# Adapter-IOX-test.net
KiCad netlist of a schematic drawn in EAGLE
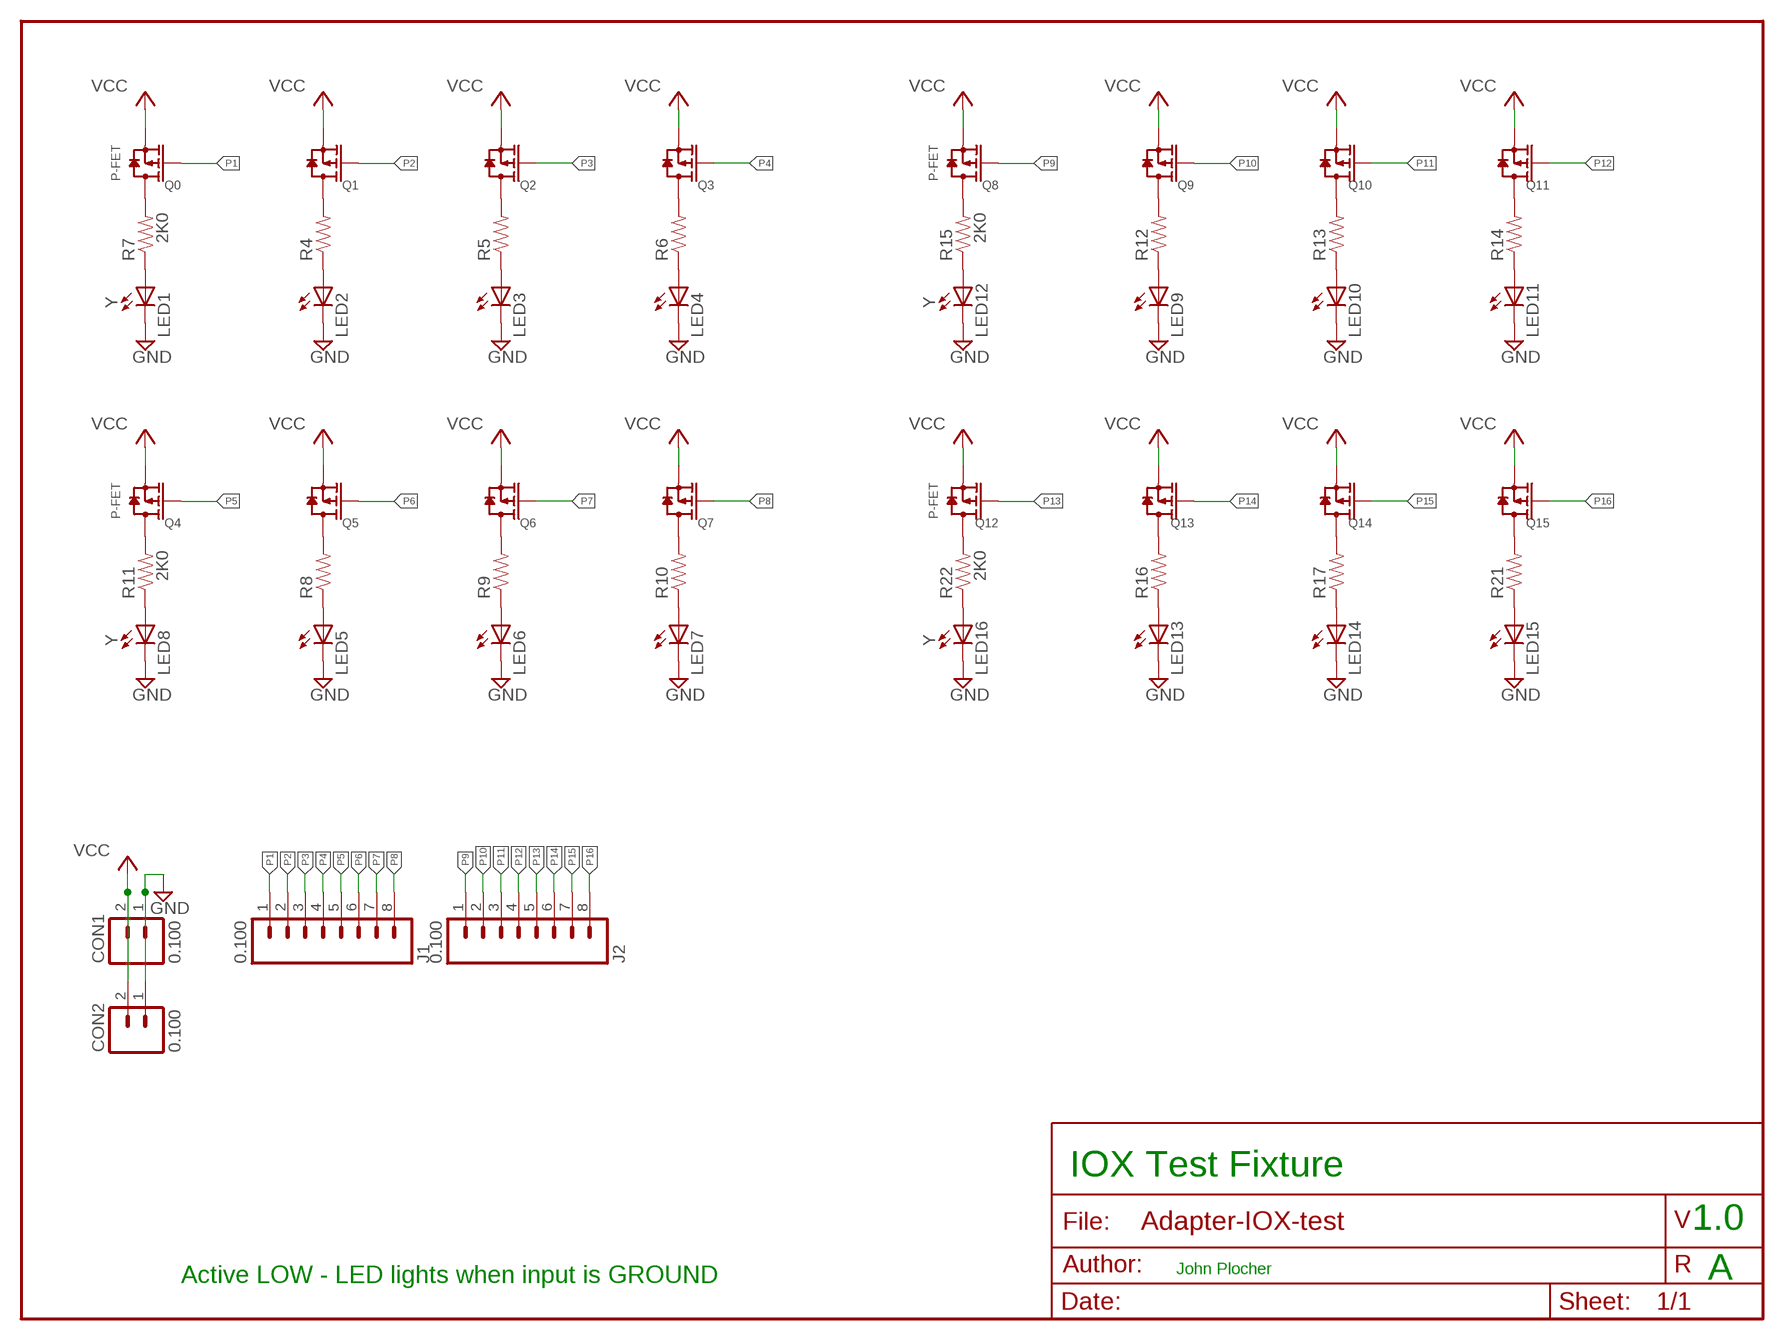
[diagram p0: schematic, sheet 1]

(export (version "E")
  (design (tool "Eeschema 10.0.6"))
  (components
    (comp (ref "CON1")
      (value "0.100")
      (footprint "eagle-import:1X02_LOCK")
      (libsource (lib "eagle-import") (part "CONNECTOR-M021X02-LOCK"))
    )
    (comp (ref "CON2")
      (value "0.100")
      (footprint "eagle-import:1X02_LOCK")
      (libsource (lib "eagle-import") (part "CONNECTOR-M021X02-LOCK"))
    )
    (comp (ref "J1")
      (value "0.100")
      (footprint "eagle-import:1X08_LOCK")
      (libsource (lib "eagle-import") (part "CONNECTOR-M08LOCK"))
    )
    (comp (ref "J2")
      (value "0.100")
      (footprint "eagle-import:1X08_LOCK")
      (libsource (lib "eagle-import") (part "CONNECTOR-M08LOCK"))
    )
    (comp (ref "LED1")
      (value "Y")
      (footprint "eagle-import:0603-LED")
      (libsource (lib "eagle-import") (part "LED0603-LED"))
    )
    (comp (ref "LED2")
      (value "Y")
      (footprint "eagle-import:0603-LED")
      (libsource (lib "eagle-import") (part "LED0603-LED"))
    )
    (comp (ref "LED3")
      (value "Y")
      (footprint "eagle-import:0603-LED")
      (libsource (lib "eagle-import") (part "LED0603-LED"))
    )
    (comp (ref "LED4")
      (value "Y")
      (footprint "eagle-import:0603-LED")
      (libsource (lib "eagle-import") (part "LED0603-LED"))
    )
    (comp (ref "LED5")
      (value "Y")
      (footprint "eagle-import:0603-LED")
      (libsource (lib "eagle-import") (part "LED0603-LED"))
    )
    (comp (ref "LED6")
      (value "Y")
      (footprint "eagle-import:0603-LED")
      (libsource (lib "eagle-import") (part "LED0603-LED"))
    )
    (comp (ref "LED7")
      (value "Y")
      (footprint "eagle-import:0603-LED")
      (libsource (lib "eagle-import") (part "LED0603-LED"))
    )
    (comp (ref "LED8")
      (value "Y")
      (footprint "eagle-import:0603-LED")
      (libsource (lib "eagle-import") (part "LED0603-LED"))
    )
    (comp (ref "LED9")
      (value "Y")
      (footprint "eagle-import:0603-LED")
      (libsource (lib "eagle-import") (part "LED0603-LED"))
    )
    (comp (ref "LED10")
      (value "Y")
      (footprint "eagle-import:0603-LED")
      (libsource (lib "eagle-import") (part "LED0603-LED"))
    )
    (comp (ref "LED11")
      (value "Y")
      (footprint "eagle-import:0603-LED")
      (libsource (lib "eagle-import") (part "LED0603-LED"))
    )
    (comp (ref "LED12")
      (value "Y")
      (footprint "eagle-import:0603-LED")
      (libsource (lib "eagle-import") (part "LED0603-LED"))
    )
    (comp (ref "LED13")
      (value "Y")
      (footprint "eagle-import:0603-LED")
      (libsource (lib "eagle-import") (part "LED0603-LED"))
    )
    (comp (ref "LED14")
      (value "Y")
      (footprint "eagle-import:0603-LED")
      (libsource (lib "eagle-import") (part "LED0603-LED"))
    )
    (comp (ref "LED15")
      (value "Y")
      (footprint "eagle-import:0603-LED")
      (libsource (lib "eagle-import") (part "LED0603-LED"))
    )
    (comp (ref "LED16")
      (value "Y")
      (footprint "eagle-import:0603-LED")
      (libsource (lib "eagle-import") (part "LED0603-LED"))
    )
    (comp (ref "Q0")
      (value "P-FET")
      (footprint "eagle-import:SOT23")
      (libsource (lib "eagle-import") (part "MOSFET-P-044021001"))
    )
    (comp (ref "Q1")
      (value "P-FET")
      (footprint "eagle-import:SOT23")
      (libsource (lib "eagle-import") (part "MOSFET-P-044021001"))
    )
    (comp (ref "Q2")
      (value "P-FET")
      (footprint "eagle-import:SOT23")
      (libsource (lib "eagle-import") (part "MOSFET-P-044021001"))
    )
    (comp (ref "Q3")
      (value "P-FET")
      (footprint "eagle-import:SOT23")
      (libsource (lib "eagle-import") (part "MOSFET-P-044021001"))
    )
    (comp (ref "Q4")
      (value "P-FET")
      (footprint "eagle-import:SOT23")
      (libsource (lib "eagle-import") (part "MOSFET-P-044021001"))
    )
    (comp (ref "Q5")
      (value "P-FET")
      (footprint "eagle-import:SOT23")
      (libsource (lib "eagle-import") (part "MOSFET-P-044021001"))
    )
    (comp (ref "Q6")
      (value "P-FET")
      (footprint "eagle-import:SOT23")
      (libsource (lib "eagle-import") (part "MOSFET-P-044021001"))
    )
    (comp (ref "Q7")
      (value "P-FET")
      (footprint "eagle-import:SOT23")
      (libsource (lib "eagle-import") (part "MOSFET-P-044021001"))
    )
    (comp (ref "Q8")
      (value "P-FET")
      (footprint "eagle-import:SOT23")
      (libsource (lib "eagle-import") (part "MOSFET-P-044021001"))
    )
    (comp (ref "Q9")
      (value "P-FET")
      (footprint "eagle-import:SOT23")
      (libsource (lib "eagle-import") (part "MOSFET-P-044021001"))
    )
    (comp (ref "Q10")
      (value "P-FET")
      (footprint "eagle-import:SOT23")
      (libsource (lib "eagle-import") (part "MOSFET-P-044021001"))
    )
    (comp (ref "Q11")
      (value "P-FET")
      (footprint "eagle-import:SOT23")
      (libsource (lib "eagle-import") (part "MOSFET-P-044021001"))
    )
    (comp (ref "Q12")
      (value "P-FET")
      (footprint "eagle-import:SOT23")
      (libsource (lib "eagle-import") (part "MOSFET-P-044021001"))
    )
    (comp (ref "Q13")
      (value "P-FET")
      (footprint "eagle-import:SOT23")
      (libsource (lib "eagle-import") (part "MOSFET-P-044021001"))
    )
    (comp (ref "Q14")
      (value "P-FET")
      (footprint "eagle-import:SOT23")
      (libsource (lib "eagle-import") (part "MOSFET-P-044021001"))
    )
    (comp (ref "Q15")
      (value "P-FET")
      (footprint "eagle-import:SOT23")
      (libsource (lib "eagle-import") (part "MOSFET-P-044021001"))
    )
    (comp (ref "R4")
      (value "2K0")
      (footprint "eagle-import:0805-RES")
      (libsource (lib "eagle-import") (part "R0805-RES"))
    )
    (comp (ref "R5")
      (value "2K0")
      (footprint "eagle-import:0805-RES")
      (libsource (lib "eagle-import") (part "R0805-RES"))
    )
    (comp (ref "R6")
      (value "2K0")
      (footprint "eagle-import:0805-RES")
      (libsource (lib "eagle-import") (part "R0805-RES"))
    )
    (comp (ref "R7")
      (value "2K0")
      (footprint "eagle-import:0805-RES")
      (libsource (lib "eagle-import") (part "R0805-RES"))
    )
    (comp (ref "R8")
      (value "2K0")
      (footprint "eagle-import:0805-RES")
      (libsource (lib "eagle-import") (part "R0805-RES"))
    )
    (comp (ref "R9")
      (value "2K0")
      (footprint "eagle-import:0805-RES")
      (libsource (lib "eagle-import") (part "R0805-RES"))
    )
    (comp (ref "R10")
      (value "2K0")
      (footprint "eagle-import:0805-RES")
      (libsource (lib "eagle-import") (part "R0805-RES"))
    )
    (comp (ref "R11")
      (value "2K0")
      (footprint "eagle-import:0805-RES")
      (libsource (lib "eagle-import") (part "R0805-RES"))
    )
    (comp (ref "R12")
      (value "2K0")
      (footprint "eagle-import:0805-RES")
      (libsource (lib "eagle-import") (part "R0805-RES"))
    )
    (comp (ref "R13")
      (value "2K0")
      (footprint "eagle-import:0805-RES")
      (libsource (lib "eagle-import") (part "R0805-RES"))
    )
    (comp (ref "R14")
      (value "2K0")
      (footprint "eagle-import:0805-RES")
      (libsource (lib "eagle-import") (part "R0805-RES"))
    )
    (comp (ref "R15")
      (value "2K0")
      (footprint "eagle-import:0805-RES")
      (libsource (lib "eagle-import") (part "R0805-RES"))
    )
    (comp (ref "R16")
      (value "2K0")
      (footprint "eagle-import:0805-RES")
      (libsource (lib "eagle-import") (part "R0805-RES"))
    )
    (comp (ref "R17")
      (value "2K0")
      (footprint "eagle-import:0805-RES")
      (libsource (lib "eagle-import") (part "R0805-RES"))
    )
    (comp (ref "R21")
      (value "2K0")
      (footprint "eagle-import:0805-RES")
      (libsource (lib "eagle-import") (part "R0805-RES"))
    )
    (comp (ref "R22")
      (value "2K0")
      (footprint "eagle-import:0805-RES")
      (libsource (lib "eagle-import") (part "R0805-RES"))
    )
  )
  (nets
    (net (code "1") (name "GND") (class "Default")
      (node (ref "CON1") (pin "1") (pinfunction "A_1") (pintype "passive"))
      (node (ref "CON2") (pin "1") (pinfunction "A_1") (pintype "passive"))
      (node (ref "LED1") (pin "C") (pinfunction "C_C") (pintype "passive"))
      (node (ref "LED10") (pin "C") (pinfunction "C_C") (pintype "passive"))
      (node (ref "LED11") (pin "C") (pinfunction "C_C") (pintype "passive"))
      (node (ref "LED12") (pin "C") (pinfunction "C_C") (pintype "passive"))
      (node (ref "LED13") (pin "C") (pinfunction "C_C") (pintype "passive"))
      (node (ref "LED14") (pin "C") (pinfunction "C_C") (pintype "passive"))
      (node (ref "LED15") (pin "C") (pinfunction "C_C") (pintype "passive"))
      (node (ref "LED16") (pin "C") (pinfunction "C_C") (pintype "passive"))
      (node (ref "LED2") (pin "C") (pinfunction "C_C") (pintype "passive"))
      (node (ref "LED3") (pin "C") (pinfunction "C_C") (pintype "passive"))
      (node (ref "LED4") (pin "C") (pinfunction "C_C") (pintype "passive"))
      (node (ref "LED5") (pin "C") (pinfunction "C_C") (pintype "passive"))
      (node (ref "LED6") (pin "C") (pinfunction "C_C") (pintype "passive"))
      (node (ref "LED7") (pin "C") (pinfunction "C_C") (pintype "passive"))
      (node (ref "LED8") (pin "C") (pinfunction "C_C") (pintype "passive"))
      (node (ref "LED9") (pin "C") (pinfunction "C_C") (pintype "passive"))
    )
    (net (code "2") (name "Net-(LED1-PadA)") (class "Default")
      (node (ref "LED1") (pin "A") (pinfunction "A_A") (pintype "passive"))
      (node (ref "R7") (pin "1") (pinfunction "1_1") (pintype "passive"))
    )
    (net (code "3") (name "Net-(LED2-PadA)") (class "Default")
      (node (ref "LED2") (pin "A") (pinfunction "A_A") (pintype "passive"))
      (node (ref "R4") (pin "1") (pinfunction "1_1") (pintype "passive"))
    )
    (net (code "4") (name "Net-(LED3-PadA)") (class "Default")
      (node (ref "LED3") (pin "A") (pinfunction "A_A") (pintype "passive"))
      (node (ref "R5") (pin "1") (pinfunction "1_1") (pintype "passive"))
    )
    (net (code "5") (name "Net-(LED4-PadA)") (class "Default")
      (node (ref "LED4") (pin "A") (pinfunction "A_A") (pintype "passive"))
      (node (ref "R6") (pin "1") (pinfunction "1_1") (pintype "passive"))
    )
    (net (code "6") (name "Net-(LED5-PadA)") (class "Default")
      (node (ref "LED5") (pin "A") (pinfunction "A_A") (pintype "passive"))
      (node (ref "R8") (pin "1") (pinfunction "1_1") (pintype "passive"))
    )
    (net (code "7") (name "Net-(LED6-PadA)") (class "Default")
      (node (ref "LED6") (pin "A") (pinfunction "A_A") (pintype "passive"))
      (node (ref "R9") (pin "1") (pinfunction "1_1") (pintype "passive"))
    )
    (net (code "8") (name "Net-(LED7-PadA)") (class "Default")
      (node (ref "LED7") (pin "A") (pinfunction "A_A") (pintype "passive"))
      (node (ref "R10") (pin "1") (pinfunction "1_1") (pintype "passive"))
    )
    (net (code "9") (name "Net-(LED8-PadA)") (class "Default")
      (node (ref "LED8") (pin "A") (pinfunction "A_A") (pintype "passive"))
      (node (ref "R11") (pin "1") (pinfunction "1_1") (pintype "passive"))
    )
    (net (code "10") (name "Net-(LED9-PadA)") (class "Default")
      (node (ref "LED9") (pin "A") (pinfunction "A_A") (pintype "passive"))
      (node (ref "R12") (pin "1") (pinfunction "1_1") (pintype "passive"))
    )
    (net (code "11") (name "Net-(LED10-PadA)") (class "Default")
      (node (ref "LED10") (pin "A") (pinfunction "A_A") (pintype "passive"))
      (node (ref "R13") (pin "1") (pinfunction "1_1") (pintype "passive"))
    )
    (net (code "12") (name "Net-(LED11-PadA)") (class "Default")
      (node (ref "LED11") (pin "A") (pinfunction "A_A") (pintype "passive"))
      (node (ref "R14") (pin "1") (pinfunction "1_1") (pintype "passive"))
    )
    (net (code "13") (name "Net-(LED12-PadA)") (class "Default")
      (node (ref "LED12") (pin "A") (pinfunction "A_A") (pintype "passive"))
      (node (ref "R15") (pin "1") (pinfunction "1_1") (pintype "passive"))
    )
    (net (code "14") (name "Net-(LED13-PadA)") (class "Default")
      (node (ref "LED13") (pin "A") (pinfunction "A_A") (pintype "passive"))
      (node (ref "R16") (pin "1") (pinfunction "1_1") (pintype "passive"))
    )
    (net (code "15") (name "Net-(LED14-PadA)") (class "Default")
      (node (ref "LED14") (pin "A") (pinfunction "A_A") (pintype "passive"))
      (node (ref "R17") (pin "1") (pinfunction "1_1") (pintype "passive"))
    )
    (net (code "16") (name "Net-(LED15-PadA)") (class "Default")
      (node (ref "LED15") (pin "A") (pinfunction "A_A") (pintype "passive"))
      (node (ref "R21") (pin "1") (pinfunction "1_1") (pintype "passive"))
    )
    (net (code "17") (name "Net-(LED16-PadA)") (class "Default")
      (node (ref "LED16") (pin "A") (pinfunction "A_A") (pintype "passive"))
      (node (ref "R22") (pin "1") (pinfunction "1_1") (pintype "passive"))
    )
    (net (code "18") (name "Net-(Q0-D)") (class "Default")
      (node (ref "Q0") (pin "3") (pinfunction "D_3") (pintype "passive"))
      (node (ref "R7") (pin "2") (pinfunction "2_2") (pintype "passive"))
    )
    (net (code "19") (name "Net-(Q1-D)") (class "Default")
      (node (ref "Q1") (pin "3") (pinfunction "D_3") (pintype "passive"))
      (node (ref "R4") (pin "2") (pinfunction "2_2") (pintype "passive"))
    )
    (net (code "20") (name "Net-(Q2-D)") (class "Default")
      (node (ref "Q2") (pin "3") (pinfunction "D_3") (pintype "passive"))
      (node (ref "R5") (pin "2") (pinfunction "2_2") (pintype "passive"))
    )
    (net (code "21") (name "Net-(Q3-D)") (class "Default")
      (node (ref "Q3") (pin "3") (pinfunction "D_3") (pintype "passive"))
      (node (ref "R6") (pin "2") (pinfunction "2_2") (pintype "passive"))
    )
    (net (code "22") (name "Net-(Q4-D)") (class "Default")
      (node (ref "Q4") (pin "3") (pinfunction "D_3") (pintype "passive"))
      (node (ref "R11") (pin "2") (pinfunction "2_2") (pintype "passive"))
    )
    (net (code "23") (name "Net-(Q5-D)") (class "Default")
      (node (ref "Q5") (pin "3") (pinfunction "D_3") (pintype "passive"))
      (node (ref "R8") (pin "2") (pinfunction "2_2") (pintype "passive"))
    )
    (net (code "24") (name "Net-(Q6-D)") (class "Default")
      (node (ref "Q6") (pin "3") (pinfunction "D_3") (pintype "passive"))
      (node (ref "R9") (pin "2") (pinfunction "2_2") (pintype "passive"))
    )
    (net (code "25") (name "Net-(Q7-D)") (class "Default")
      (node (ref "Q7") (pin "3") (pinfunction "D_3") (pintype "passive"))
      (node (ref "R10") (pin "2") (pinfunction "2_2") (pintype "passive"))
    )
    (net (code "26") (name "Net-(Q8-D)") (class "Default")
      (node (ref "Q8") (pin "3") (pinfunction "D_3") (pintype "passive"))
      (node (ref "R15") (pin "2") (pinfunction "2_2") (pintype "passive"))
    )
    (net (code "27") (name "Net-(Q9-D)") (class "Default")
      (node (ref "Q9") (pin "3") (pinfunction "D_3") (pintype "passive"))
      (node (ref "R12") (pin "2") (pinfunction "2_2") (pintype "passive"))
    )
    (net (code "28") (name "Net-(Q10-D)") (class "Default")
      (node (ref "Q10") (pin "3") (pinfunction "D_3") (pintype "passive"))
      (node (ref "R13") (pin "2") (pinfunction "2_2") (pintype "passive"))
    )
    (net (code "29") (name "Net-(Q11-D)") (class "Default")
      (node (ref "Q11") (pin "3") (pinfunction "D_3") (pintype "passive"))
      (node (ref "R14") (pin "2") (pinfunction "2_2") (pintype "passive"))
    )
    (net (code "30") (name "Net-(Q12-D)") (class "Default")
      (node (ref "Q12") (pin "3") (pinfunction "D_3") (pintype "passive"))
      (node (ref "R22") (pin "2") (pinfunction "2_2") (pintype "passive"))
    )
    (net (code "31") (name "Net-(Q13-D)") (class "Default")
      (node (ref "Q13") (pin "3") (pinfunction "D_3") (pintype "passive"))
      (node (ref "R16") (pin "2") (pinfunction "2_2") (pintype "passive"))
    )
    (net (code "32") (name "Net-(Q14-D)") (class "Default")
      (node (ref "Q14") (pin "3") (pinfunction "D_3") (pintype "passive"))
      (node (ref "R17") (pin "2") (pinfunction "2_2") (pintype "passive"))
    )
    (net (code "33") (name "Net-(Q15-D)") (class "Default")
      (node (ref "Q15") (pin "3") (pinfunction "D_3") (pintype "passive"))
      (node (ref "R21") (pin "2") (pinfunction "2_2") (pintype "passive"))
    )
    (net (code "34") (name "P1") (class "Default")
      (node (ref "J1") (pin "1") (pinfunction "1_1") (pintype "passive"))
      (node (ref "Q0") (pin "1") (pinfunction "G_1") (pintype "passive"))
    )
    (net (code "35") (name "P2") (class "Default")
      (node (ref "J1") (pin "2") (pinfunction "2_2") (pintype "passive"))
      (node (ref "Q1") (pin "1") (pinfunction "G_1") (pintype "passive"))
    )
    (net (code "36") (name "P3") (class "Default")
      (node (ref "J1") (pin "3") (pinfunction "3_3") (pintype "passive"))
      (node (ref "Q2") (pin "1") (pinfunction "G_1") (pintype "passive"))
    )
    (net (code "37") (name "P4") (class "Default")
      (node (ref "J1") (pin "4") (pinfunction "4_4") (pintype "passive"))
      (node (ref "Q3") (pin "1") (pinfunction "G_1") (pintype "passive"))
    )
    (net (code "38") (name "P5") (class "Default")
      (node (ref "J1") (pin "5") (pinfunction "5_5") (pintype "passive"))
      (node (ref "Q4") (pin "1") (pinfunction "G_1") (pintype "passive"))
    )
    (net (code "39") (name "P6") (class "Default")
      (node (ref "J1") (pin "6") (pinfunction "6_6") (pintype "passive"))
      (node (ref "Q5") (pin "1") (pinfunction "G_1") (pintype "passive"))
    )
    (net (code "40") (name "P7") (class "Default")
      (node (ref "J1") (pin "7") (pinfunction "7_7") (pintype "passive"))
      (node (ref "Q6") (pin "1") (pinfunction "G_1") (pintype "passive"))
    )
    (net (code "41") (name "P8") (class "Default")
      (node (ref "J1") (pin "8") (pinfunction "8_8") (pintype "passive"))
      (node (ref "Q7") (pin "1") (pinfunction "G_1") (pintype "passive"))
    )
    (net (code "42") (name "P9") (class "Default")
      (node (ref "J2") (pin "1") (pinfunction "1_1") (pintype "passive"))
      (node (ref "Q8") (pin "1") (pinfunction "G_1") (pintype "passive"))
    )
    (net (code "43") (name "P10") (class "Default")
      (node (ref "J2") (pin "2") (pinfunction "2_2") (pintype "passive"))
      (node (ref "Q9") (pin "1") (pinfunction "G_1") (pintype "passive"))
    )
    (net (code "44") (name "P11") (class "Default")
      (node (ref "J2") (pin "3") (pinfunction "3_3") (pintype "passive"))
      (node (ref "Q10") (pin "1") (pinfunction "G_1") (pintype "passive"))
    )
    (net (code "45") (name "P12") (class "Default")
      (node (ref "J2") (pin "4") (pinfunction "4_4") (pintype "passive"))
      (node (ref "Q11") (pin "1") (pinfunction "G_1") (pintype "passive"))
    )
    (net (code "46") (name "P13") (class "Default")
      (node (ref "J2") (pin "5") (pinfunction "5_5") (pintype "passive"))
      (node (ref "Q12") (pin "1") (pinfunction "G_1") (pintype "passive"))
    )
    (net (code "47") (name "P14") (class "Default")
      (node (ref "J2") (pin "6") (pinfunction "6_6") (pintype "passive"))
      (node (ref "Q13") (pin "1") (pinfunction "G_1") (pintype "passive"))
    )
    (net (code "48") (name "P15") (class "Default")
      (node (ref "J2") (pin "7") (pinfunction "7_7") (pintype "passive"))
      (node (ref "Q14") (pin "1") (pinfunction "G_1") (pintype "passive"))
    )
    (net (code "49") (name "P16") (class "Default")
      (node (ref "J2") (pin "8") (pinfunction "8_8") (pintype "passive"))
      (node (ref "Q15") (pin "1") (pinfunction "G_1") (pintype "passive"))
    )
    (net (code "50") (name "VCC") (class "Default")
      (node (ref "CON1") (pin "2") (pinfunction "B_2") (pintype "passive"))
      (node (ref "CON2") (pin "2") (pinfunction "B_2") (pintype "passive"))
      (node (ref "Q0") (pin "2") (pinfunction "S_2") (pintype "passive"))
      (node (ref "Q1") (pin "2") (pinfunction "S_2") (pintype "passive"))
      (node (ref "Q10") (pin "2") (pinfunction "S_2") (pintype "passive"))
      (node (ref "Q11") (pin "2") (pinfunction "S_2") (pintype "passive"))
      (node (ref "Q12") (pin "2") (pinfunction "S_2") (pintype "passive"))
      (node (ref "Q13") (pin "2") (pinfunction "S_2") (pintype "passive"))
      (node (ref "Q14") (pin "2") (pinfunction "S_2") (pintype "passive"))
      (node (ref "Q15") (pin "2") (pinfunction "S_2") (pintype "passive"))
      (node (ref "Q2") (pin "2") (pinfunction "S_2") (pintype "passive"))
      (node (ref "Q3") (pin "2") (pinfunction "S_2") (pintype "passive"))
      (node (ref "Q4") (pin "2") (pinfunction "S_2") (pintype "passive"))
      (node (ref "Q5") (pin "2") (pinfunction "S_2") (pintype "passive"))
      (node (ref "Q6") (pin "2") (pinfunction "S_2") (pintype "passive"))
      (node (ref "Q7") (pin "2") (pinfunction "S_2") (pintype "passive"))
      (node (ref "Q8") (pin "2") (pinfunction "S_2") (pintype "passive"))
      (node (ref "Q9") (pin "2") (pinfunction "S_2") (pintype "passive"))
    )
  )
)
